# EHDD_LAB_4.net
KiCad netlist of a schematic drawn in EAGLE
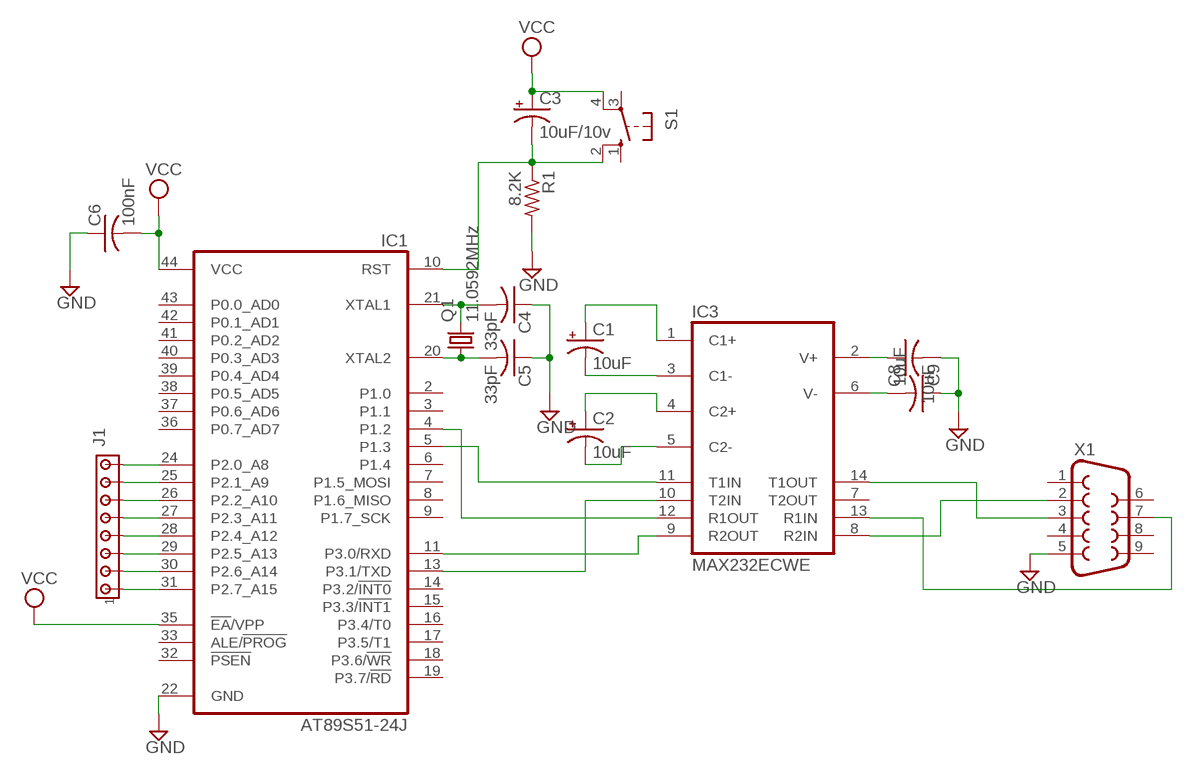
[diagram p0: schematic, sheet 1]

(export (version "E")
  (design (tool "Eeschema 10.0.6"))
  (components
    (comp (ref "C1")
      (value "10uF")
      (footprint "eagle-import:153CLV-0405")
      (libsource (lib "eagle-import") (part "CPOL-US153CLV-0405"))
    )
    (comp (ref "C2")
      (value "10uF")
      (footprint "eagle-import:153CLV-0405")
      (libsource (lib "eagle-import") (part "CPOL-US153CLV-0405"))
    )
    (comp (ref "C3")
      (value "10uF/10v")
      (footprint "eagle-import:153CLV-0405")
      (libsource (lib "eagle-import") (part "CPOL-US153CLV-0405"))
    )
    (comp (ref "C4")
      (value "33pF")
      (footprint "eagle-import:C0805")
      (libsource (lib "eagle-import") (part "C-USC0805"))
    )
    (comp (ref "C5")
      (value "33pF")
      (footprint "eagle-import:C0805")
      (libsource (lib "eagle-import") (part "C-USC0805"))
    )
    (comp (ref "C6")
      (value "100nF")
      (footprint "eagle-import:C0805")
      (libsource (lib "eagle-import") (part "C-USC0805"))
    )
    (comp (ref "C8")
      (value "10uF")
      (footprint "eagle-import:C0805")
      (libsource (lib "eagle-import") (part "C-USC0805"))
    )
    (comp (ref "C9")
      (value "10uF")
      (footprint "eagle-import:C0805")
      (libsource (lib "eagle-import") (part "C-USC0805"))
    )
    (comp (ref "IC1")
      (value "AT89S51-24J")
      (footprint "eagle-import:PLCC44")
      (fields (field (name "MPN") "AT89S51-24JU"))
      (libsource (lib "eagle-import") (part "AT89S51-J24"))
    )
    (comp (ref "IC3")
      (value "MAX232ECWE")
      (footprint "eagle-import:SO16L")
      (fields (field (name "MF") "MAXIM") (field (name "MPN") "MAX232ECWE+"))
      (libsource (lib "eagle-import") (part "MAX232ECWE"))
    )
    (comp (ref "J1")
      (value "MTA08-100")
      (footprint "eagle-import:10X08MTA")
      (libsource (lib "eagle-import") (part "MTA08-100"))
    )
    (comp (ref "Q1")
      (value "11.0592MHz")
      (footprint "eagle-import:TC38H")
      (libsource (lib "eagle-import") (part "CRYSTALTC38H"))
    )
    (comp (ref "R1")
      (value "8.2K")
      (footprint "eagle-import:R0805")
      (libsource (lib "eagle-import") (part "R-US_R0805"))
    )
    (comp (ref "S1")
      (value "10-XX")
      (footprint "eagle-import:B3F-10XX")
      (fields (field (name "MPN") "B3F-1000"))
      (libsource (lib "eagle-import") (part "10-XX"))
    )
    (comp (ref "X1")
      (value "F09V")
      (footprint "eagle-import:F09V")
      (libsource (lib "eagle-import") (part "F09V"))
    )
  )
  (nets
    (net (code "1") (name "GND") (class "Default")
      (node (ref "C4") (pin "1") (pinfunction "1_1") (pintype "passive"))
      (node (ref "C5") (pin "1") (pinfunction "1_1") (pintype "passive"))
      (node (ref "C6") (pin "1") (pinfunction "1_1") (pintype "passive"))
      (node (ref "C8") (pin "2") (pinfunction "2_2") (pintype "passive"))
      (node (ref "C9") (pin "1") (pinfunction "1_1") (pintype "passive"))
      (node (ref "IC1") (pin "22") (pinfunction "GND_22") (pintype "power_in"))
      (node (ref "R1") (pin "2") (pinfunction "2_2") (pintype "passive"))
      (node (ref "X1") (pin "5") (pinfunction "5_5") (pintype "passive"))
    )
    (net (code "2") (name "Net-(IC1-P1.2)") (class "Default")
      (node (ref "IC1") (pin "4") (pinfunction "P1.2_4") (pintype "bidirectional"))
      (node (ref "IC3") (pin "12") (pinfunction "R1OUT_12") (pintype "output"))
    )
    (net (code "3") (name "Net-(IC1-P1.3)") (class "Default")
      (node (ref "IC1") (pin "5") (pinfunction "P1.3_5") (pintype "bidirectional"))
      (node (ref "IC3") (pin "11") (pinfunction "T1IN_11") (pintype "input"))
    )
    (net (code "4") (name "Net-(IC1-P2.0_A8)") (class "Default")
      (node (ref "IC1") (pin "24") (pinfunction "P2.0_A8_24") (pintype "bidirectional"))
      (node (ref "J1") (pin "8") (pinfunction "8_8") (pintype "passive"))
    )
    (net (code "5") (name "Net-(IC1-P2.1_A9)") (class "Default")
      (node (ref "IC1") (pin "25") (pinfunction "P2.1_A9_25") (pintype "bidirectional"))
      (node (ref "J1") (pin "7") (pinfunction "7_7") (pintype "passive"))
    )
    (net (code "6") (name "Net-(IC1-P2.2_A10)") (class "Default")
      (node (ref "IC1") (pin "26") (pinfunction "P2.2_A10_26") (pintype "bidirectional"))
      (node (ref "J1") (pin "6") (pinfunction "6_6") (pintype "passive"))
    )
    (net (code "7") (name "Net-(IC1-P2.3_A11)") (class "Default")
      (node (ref "IC1") (pin "27") (pinfunction "P2.3_A11_27") (pintype "bidirectional"))
      (node (ref "J1") (pin "5") (pinfunction "5_5") (pintype "passive"))
    )
    (net (code "8") (name "Net-(IC1-P2.4_A12)") (class "Default")
      (node (ref "IC1") (pin "28") (pinfunction "P2.4_A12_28") (pintype "bidirectional"))
      (node (ref "J1") (pin "4") (pinfunction "4_4") (pintype "passive"))
    )
    (net (code "9") (name "Net-(IC1-P2.5_A13)") (class "Default")
      (node (ref "IC1") (pin "29") (pinfunction "P2.5_A13_29") (pintype "bidirectional"))
      (node (ref "J1") (pin "3") (pinfunction "3_3") (pintype "passive"))
    )
    (net (code "10") (name "Net-(IC1-P2.6_A14)") (class "Default")
      (node (ref "IC1") (pin "30") (pinfunction "P2.6_A14_30") (pintype "bidirectional"))
      (node (ref "J1") (pin "2") (pinfunction "2_2") (pintype "passive"))
    )
    (net (code "11") (name "Net-(IC1-P2.7_A15)") (class "Default")
      (node (ref "IC1") (pin "31") (pinfunction "P2.7_A15_31") (pintype "bidirectional"))
      (node (ref "J1") (pin "1") (pinfunction "1_1") (pintype "passive"))
    )
    (net (code "12") (name "Net-(IC1-P3.0{slash}RXD)") (class "Default")
      (node (ref "IC1") (pin "11") (pinfunction "P3.0/RXD_11") (pintype "bidirectional"))
      (node (ref "IC3") (pin "9") (pinfunction "R2OUT_9") (pintype "output"))
    )
    (net (code "13") (name "Net-(IC1-P3.1{slash}TXD)") (class "Default")
      (node (ref "IC1") (pin "13") (pinfunction "P3.1/TXD_13") (pintype "bidirectional"))
      (node (ref "IC3") (pin "10") (pinfunction "T2IN_10") (pintype "input"))
    )
    (net (code "14") (name "Net-(IC1-RST)") (class "Default")
      (node (ref "C3") (pin "-") (pinfunction "-_-") (pintype "passive"))
      (node (ref "IC1") (pin "10") (pinfunction "RST_10") (pintype "input"))
      (node (ref "R1") (pin "1") (pinfunction "1_1") (pintype "passive"))
      (node (ref "S1") (pin "2") (pinfunction "S1_2") (pintype "passive"))
    )
    (net (code "15") (name "Net-(IC1-XTAL1)") (class "Default")
      (node (ref "C4") (pin "2") (pinfunction "2_2") (pintype "passive"))
      (node (ref "IC1") (pin "21") (pinfunction "XTAL1_21") (pintype "input"))
      (node (ref "Q1") (pin "2") (pinfunction "2_2") (pintype "passive"))
    )
    (net (code "16") (name "Net-(IC1-XTAL2)") (class "Default")
      (node (ref "C5") (pin "2") (pinfunction "2_2") (pintype "passive"))
      (node (ref "IC1") (pin "20") (pinfunction "XTAL2_20") (pintype "input"))
      (node (ref "Q1") (pin "1") (pinfunction "1_1") (pintype "passive"))
    )
    (net (code "17") (name "Net-(IC3A-C1+)") (class "Default")
      (node (ref "C1") (pin "+") (pinfunction "+_+") (pintype "passive"))
      (node (ref "IC3") (pin "1") (pinfunction "C1+_1") (pintype "bidirectional"))
    )
    (net (code "18") (name "Net-(IC3A-C1-)") (class "Default")
      (node (ref "C1") (pin "-") (pinfunction "-_-") (pintype "passive"))
      (node (ref "IC3") (pin "3") (pinfunction "C1-_3") (pintype "bidirectional"))
    )
    (net (code "19") (name "Net-(IC3A-C2+)") (class "Default")
      (node (ref "C2") (pin "+") (pinfunction "+_+") (pintype "passive"))
      (node (ref "IC3") (pin "4") (pinfunction "C2+_4") (pintype "bidirectional"))
    )
    (net (code "20") (name "Net-(IC3A-C2-)") (class "Default")
      (node (ref "C2") (pin "-") (pinfunction "-_-") (pintype "passive"))
      (node (ref "IC3") (pin "5") (pinfunction "C2-_5") (pintype "bidirectional"))
    )
    (net (code "21") (name "Net-(IC3A-R1IN)") (class "Default")
      (node (ref "IC3") (pin "13") (pinfunction "R1IN_13") (pintype "input"))
      (node (ref "X1") (pin "7") (pinfunction "7_7") (pintype "passive"))
    )
    (net (code "22") (name "Net-(IC3A-R2IN)") (class "Default")
      (node (ref "IC3") (pin "8") (pinfunction "R2IN_8") (pintype "input"))
      (node (ref "X1") (pin "2") (pinfunction "2_2") (pintype "passive"))
    )
    (net (code "23") (name "Net-(IC3A-T1OUT)") (class "Default")
      (node (ref "IC3") (pin "14") (pinfunction "T1OUT_14") (pintype "output"))
      (node (ref "X1") (pin "3") (pinfunction "3_3") (pintype "passive"))
    )
    (net (code "24") (name "Net-(IC3A-V+)") (class "Default")
      (node (ref "C8") (pin "1") (pinfunction "1_1") (pintype "passive"))
      (node (ref "IC3") (pin "2") (pinfunction "V+_2") (pintype "bidirectional"))
    )
    (net (code "25") (name "Net-(IC3A-V-)") (class "Default")
      (node (ref "C9") (pin "2") (pinfunction "2_2") (pintype "passive"))
      (node (ref "IC3") (pin "6") (pinfunction "V-_6") (pintype "bidirectional"))
    )
    (net (code "26") (name "VCC") (class "Default")
      (node (ref "C3") (pin "+") (pinfunction "+_+") (pintype "passive"))
      (node (ref "C6") (pin "2") (pinfunction "2_2") (pintype "passive"))
      (node (ref "IC1") (pin "35") (pinfunction "~{EA}/VPP_35") (pintype "input"))
      (node (ref "IC1") (pin "44") (pinfunction "VCC_44") (pintype "power_in"))
      (node (ref "S1") (pin "4") (pinfunction "P1_4") (pintype "passive"))
    )
    (net (code "27") (name "unconnected-(IC1-ALE{slash}~{PROG}-Pad33)") (class "Default")
      (node (ref "IC1") (pin "33") (pinfunction "ALE/~{PROG}_33") (pintype "output"))
    )
    (net (code "28") (name "unconnected-(IC1-P0.0_AD0-Pad43)") (class "Default")
      (node (ref "IC1") (pin "43") (pinfunction "P0.0_AD0_43") (pintype "bidirectional"))
    )
    (net (code "29") (name "unconnected-(IC1-P0.1_AD1-Pad42)") (class "Default")
      (node (ref "IC1") (pin "42") (pinfunction "P0.1_AD1_42") (pintype "bidirectional"))
    )
    (net (code "30") (name "unconnected-(IC1-P0.2_AD2-Pad41)") (class "Default")
      (node (ref "IC1") (pin "41") (pinfunction "P0.2_AD2_41") (pintype "bidirectional"))
    )
    (net (code "31") (name "unconnected-(IC1-P0.3_AD3-Pad40)") (class "Default")
      (node (ref "IC1") (pin "40") (pinfunction "P0.3_AD3_40") (pintype "bidirectional"))
    )
    (net (code "32") (name "unconnected-(IC1-P0.4_AD4-Pad39)") (class "Default")
      (node (ref "IC1") (pin "39") (pinfunction "P0.4_AD4_39") (pintype "bidirectional"))
    )
    (net (code "33") (name "unconnected-(IC1-P0.5_AD5-Pad38)") (class "Default")
      (node (ref "IC1") (pin "38") (pinfunction "P0.5_AD5_38") (pintype "bidirectional"))
    )
    (net (code "34") (name "unconnected-(IC1-P0.6_AD6-Pad37)") (class "Default")
      (node (ref "IC1") (pin "37") (pinfunction "P0.6_AD6_37") (pintype "bidirectional"))
    )
    (net (code "35") (name "unconnected-(IC1-P0.7_AD7-Pad36)") (class "Default")
      (node (ref "IC1") (pin "36") (pinfunction "P0.7_AD7_36") (pintype "bidirectional"))
    )
    (net (code "36") (name "unconnected-(IC1-P1.0-Pad2)") (class "Default")
      (node (ref "IC1") (pin "2") (pinfunction "P1.0_2") (pintype "bidirectional"))
    )
    (net (code "37") (name "unconnected-(IC1-P1.1-Pad3)") (class "Default")
      (node (ref "IC1") (pin "3") (pinfunction "P1.1_3") (pintype "bidirectional"))
    )
    (net (code "38") (name "unconnected-(IC1-P1.4-Pad6)") (class "Default")
      (node (ref "IC1") (pin "6") (pinfunction "P1.4_6") (pintype "bidirectional"))
    )
    (net (code "39") (name "unconnected-(IC1-P1.5_MOSI-Pad7)") (class "Default")
      (node (ref "IC1") (pin "7") (pinfunction "P1.5_MOSI_7") (pintype "bidirectional"))
    )
    (net (code "40") (name "unconnected-(IC1-P1.6_MISO-Pad8)") (class "Default")
      (node (ref "IC1") (pin "8") (pinfunction "P1.6_MISO_8") (pintype "bidirectional"))
    )
    (net (code "41") (name "unconnected-(IC1-P1.7_SCK-Pad9)") (class "Default")
      (node (ref "IC1") (pin "9") (pinfunction "P1.7_SCK_9") (pintype "bidirectional"))
    )
    (net (code "42") (name "unconnected-(IC1-P3.2{slash}~{INT0}-Pad14)") (class "Default")
      (node (ref "IC1") (pin "14") (pinfunction "P3.2/~{INT0}_14") (pintype "bidirectional"))
    )
    (net (code "43") (name "unconnected-(IC1-P3.3{slash}~{INT1}-Pad15)") (class "Default")
      (node (ref "IC1") (pin "15") (pinfunction "P3.3/~{INT1}_15") (pintype "bidirectional"))
    )
    (net (code "44") (name "unconnected-(IC1-P3.4{slash}T0-Pad16)") (class "Default")
      (node (ref "IC1") (pin "16") (pinfunction "P3.4/T0_16") (pintype "bidirectional"))
    )
    (net (code "45") (name "unconnected-(IC1-P3.5{slash}T1-Pad17)") (class "Default")
      (node (ref "IC1") (pin "17") (pinfunction "P3.5/T1_17") (pintype "bidirectional"))
    )
    (net (code "46") (name "unconnected-(IC1-P3.6{slash}~{WR}-Pad18)") (class "Default")
      (node (ref "IC1") (pin "18") (pinfunction "P3.6/~{WR}_18") (pintype "bidirectional"))
    )
    (net (code "47") (name "unconnected-(IC1-P3.7{slash}~{RD}-Pad19)") (class "Default")
      (node (ref "IC1") (pin "19") (pinfunction "P3.7/~{RD}_19") (pintype "bidirectional"))
    )
    (net (code "48") (name "unconnected-(IC1-~{PSEN}-Pad32)") (class "Default")
      (node (ref "IC1") (pin "32") (pinfunction "~{PSEN}_32") (pintype "output"))
    )
    (net (code "49") (name "unconnected-(IC3A-T2OUT-Pad7)") (class "Default")
      (node (ref "IC3") (pin "7") (pinfunction "T2OUT_7") (pintype "output"))
    )
    (net (code "50") (name "unconnected-(S1-P-Pad3)") (class "Default")
      (node (ref "S1") (pin "3") (pinfunction "P_3") (pintype "passive"))
    )
    (net (code "51") (name "unconnected-(S1-S-Pad1)") (class "Default")
      (node (ref "S1") (pin "1") (pinfunction "S_1") (pintype "passive"))
    )
    (net (code "52") (name "unconnected-(X1-Pad1)") (class "Default")
      (node (ref "X1") (pin "1") (pinfunction "1_1") (pintype "passive"))
    )
    (net (code "53") (name "unconnected-(X1-Pad4)") (class "Default")
      (node (ref "X1") (pin "4") (pinfunction "4_4") (pintype "passive"))
    )
    (net (code "54") (name "unconnected-(X1-Pad6)") (class "Default")
      (node (ref "X1") (pin "6") (pinfunction "6_6") (pintype "passive"))
    )
    (net (code "55") (name "unconnected-(X1-Pad8)") (class "Default")
      (node (ref "X1") (pin "8") (pinfunction "8_8") (pintype "passive"))
    )
    (net (code "56") (name "unconnected-(X1-Pad9)") (class "Default")
      (node (ref "X1") (pin "9") (pinfunction "9_9") (pintype "passive"))
    )
  )
)
